# Power.net
KiCad netlist of a schematic drawn in Altium Designer
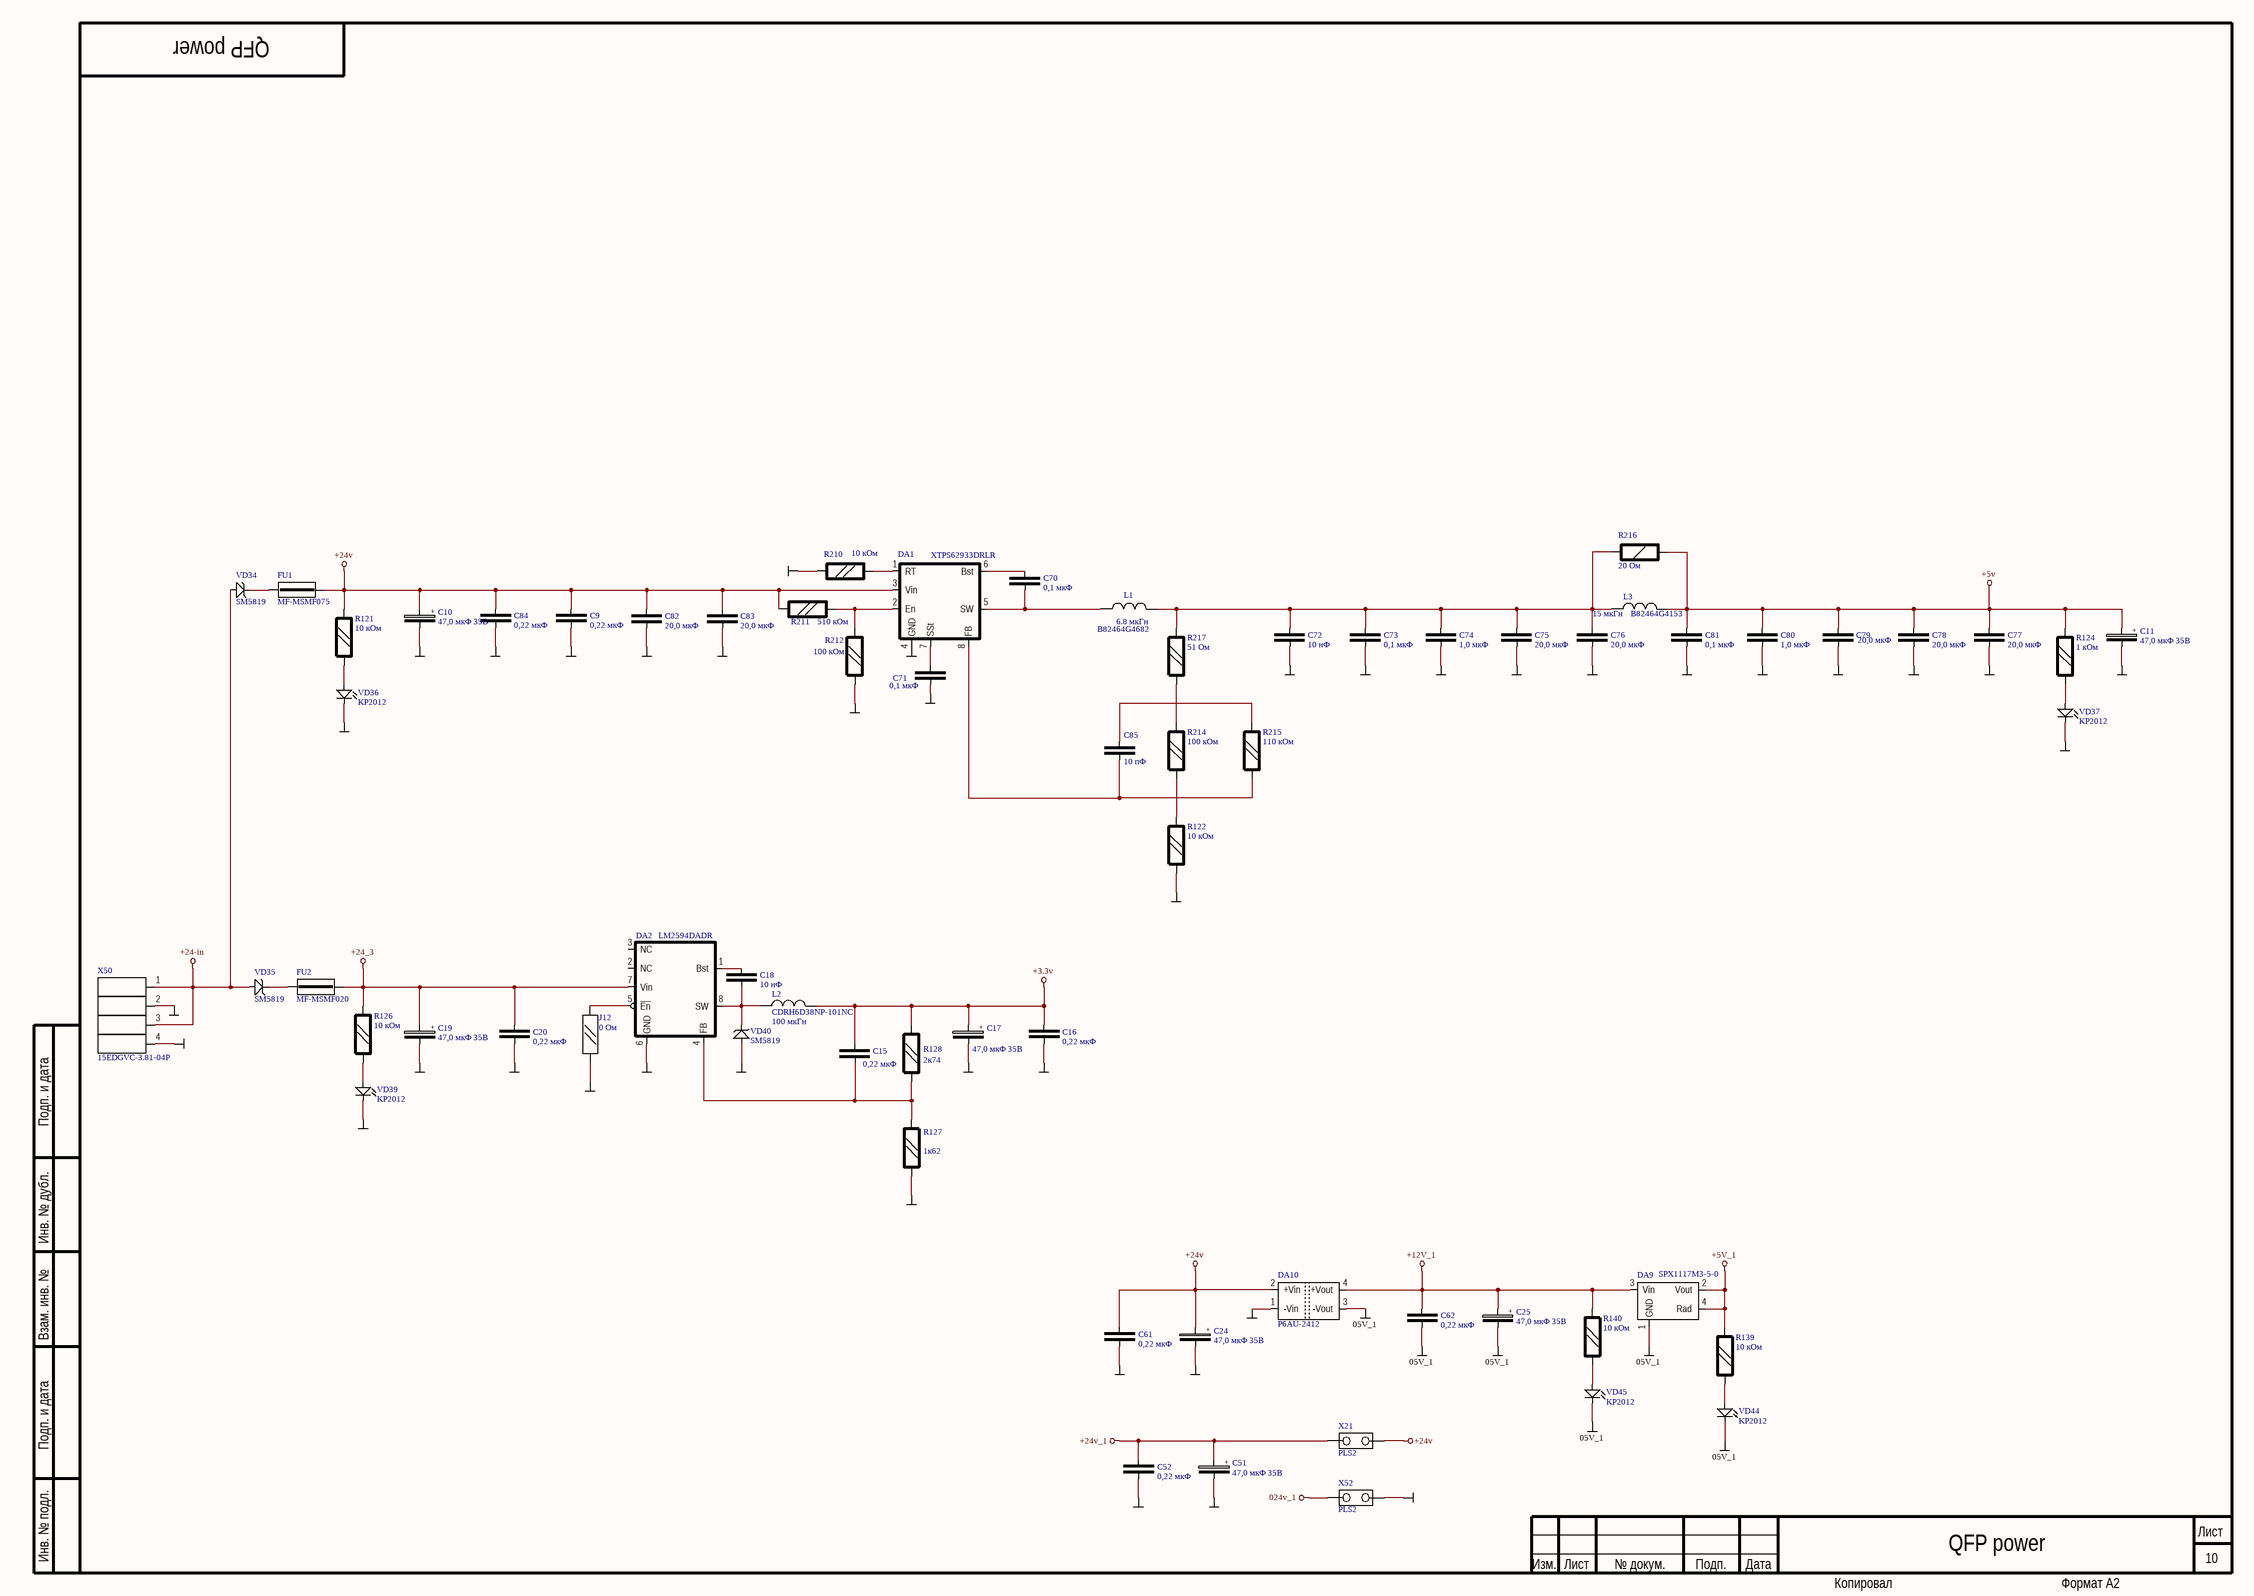
[diagram p0: Power.SchDoc]

(export (version "E")
  (design (tool "Eeschema 10.0.6"))
  (components
    (comp (ref "C9")
      (value "0,22 мкФ")
      (footprint "RC0805")
      (description "Чип конденсатор 0805")
      (fields (field (name "VOLTAGE") "50V"))
      (libsource (lib "L02_22F") (part "C0805Big"))
    )
    (comp (ref "C10")
      (value "47,0 мкФ 35В")
      (footprint "cap6")
      (description "5мм Электролитический конденсатор")
      (libsource (lib "SL02_22F") (part "C_e"))
    )
    (comp (ref "C11")
      (value "47,0 мкФ 35В")
      (footprint "cap6")
      (description "5мм Электролитический конденсатор")
      (libsource (lib "SL02_22F") (part "C_e"))
    )
    (comp (ref "C15")
      (value "0,22 мкФ")
      (footprint "SMD0805CAP")
      (description "Чип конденсатор 0805")
      (fields (field (name "VOLTAGE") "50V"))
      (libsource (lib "L02_22F") (part "C0805"))
    )
    (comp (ref "C16")
      (value "0,22 мкФ")
      (footprint "RC0805")
      (description "Чип конденсатор 0805")
      (fields (field (name "VOLTAGE") "50V"))
      (libsource (lib "L02_22F") (part "C0805Big"))
    )
    (comp (ref "C17")
      (value "47,0 мкФ 35В")
      (footprint "cap6")
      (description "5мм Электролитический конденсатор")
      (libsource (lib "SL02_22F") (part "C_e"))
    )
    (comp (ref "C18")
      (value "10 нФ")
      (footprint "RC0805")
      (description "Чип конденсатор 0805")
      (fields (field (name "VOLTAGE") "50V"))
      (libsource (lib "L02_22F") (part "C0805Big"))
    )
    (comp (ref "C19")
      (value "47,0 мкФ 35В")
      (footprint "cap6")
      (description "5мм Электролитический конденсатор")
      (libsource (lib "SL02_22F") (part "C_e"))
    )
    (comp (ref "C20")
      (value "0,22 мкФ")
      (footprint "RC0805")
      (description "Чип конденсатор 0805")
      (fields (field (name "VOLTAGE") "50V"))
      (libsource (lib "L02_22F") (part "C0805Big"))
    )
    (comp (ref "C24")
      (value "47,0 мкФ 35В")
      (footprint "cap6")
      (description "5мм Электролитический конденсатор")
      (libsource (lib "SL02_22F") (part "C_e"))
    )
    (comp (ref "C25")
      (value "47,0 мкФ 35В")
      (footprint "cap6")
      (description "5мм Электролитический конденсатор")
      (libsource (lib "SL02_22F") (part "C_e"))
    )
    (comp (ref "C51")
      (value "47,0 мкФ 35В")
      (footprint "cap6")
      (description "5мм Электролитический конденсатор")
      (libsource (lib "SL02_22F") (part "C_e"))
    )
    (comp (ref "C52")
      (value "0,22 мкФ")
      (footprint "SMD0805CAP")
      (description "Чип конденсатор 0805")
      (fields (field (name "VOLTAGE") "50V"))
      (libsource (lib "SL02_22F") (part "C0805"))
    )
    (comp (ref "C61")
      (value "0,22 мкФ")
      (footprint "SMD0805CAP")
      (description "Чип конденсатор 0805")
      (fields (field (name "VOLTAGE") "50V"))
      (libsource (lib "SL02_22F") (part "C0805"))
    )
    (comp (ref "C62")
      (value "0,22 мкФ")
      (footprint "SMD0805CAP")
      (description "Чип конденсатор 0805")
      (fields (field (name "VOLTAGE") "50V"))
      (libsource (lib "SL02_22F") (part "C0805"))
    )
    (comp (ref "C70")
      (value "0,1 мкФ")
      (footprint "SMD0805CAP")
      (description "Чип конденсатор 0805")
      (fields (field (name "VOLTAGE") "50V"))
      (libsource (lib "L02_22F") (part "C0805"))
    )
    (comp (ref "C71")
      (value "0,1 мкФ")
      (footprint "SMD0805CAP")
      (description "Чип конденсатор 0805")
      (fields (field (name "VOLTAGE") "50V"))
      (libsource (lib "L02_22F") (part "C0805"))
    )
    (comp (ref "C72")
      (value "10 нФ")
      (footprint "SMD0805CAP")
      (description "Чип конденсатор 0805")
      (fields (field (name "VOLTAGE") "50V"))
      (libsource (lib "L02_22F") (part "C0805"))
    )
    (comp (ref "C73")
      (value "0,1 мкФ")
      (footprint "SMD0805CAP")
      (description "Чип конденсатор 0805")
      (fields (field (name "VOLTAGE") "50V"))
      (libsource (lib "L02_22F") (part "C0805"))
    )
    (comp (ref "C74")
      (value "1,0 мкФ")
      (footprint "SMD0805CAP")
      (description "Чип конденсатор 0805")
      (fields (field (name "VOLTAGE") "50V"))
      (libsource (lib "L02_22F") (part "C0805"))
    )
    (comp (ref "C75")
      (value "20,0 мкФ")
      (footprint "CAPC1206")
      (description "Чип конденсатор 0805")
      (fields (field (name "VOLTAGE") "25V"))
      (libsource (lib "L02_22F") (part "C1206"))
    )
    (comp (ref "C76")
      (value "20,0 мкФ")
      (footprint "CAPC1206")
      (description "Чип конденсатор 0805")
      (fields (field (name "VOLTAGE") "25V"))
      (libsource (lib "L02_22F") (part "C1206"))
    )
    (comp (ref "C77")
      (value "20,0 мкФ")
      (footprint "CAPC1206")
      (description "Чип конденсатор 0805")
      (fields (field (name "VOLTAGE") "25V"))
      (libsource (lib "L02_22F") (part "C1206"))
    )
    (comp (ref "C78")
      (value "20,0 мкФ")
      (footprint "CAPC1206")
      (description "Чип конденсатор 0805")
      (fields (field (name "VOLTAGE") "25V"))
      (libsource (lib "L02_22F") (part "C1206"))
    )
    (comp (ref "C79")
      (value "20,0 мкФ")
      (footprint "CAPC1206")
      (description "Чип конденсатор 0805")
      (fields (field (name "VOLTAGE") "25V"))
      (libsource (lib "L02_22F") (part "C1206"))
    )
    (comp (ref "C80")
      (value "1,0 мкФ")
      (footprint "SMD0805CAP")
      (description "Чип конденсатор 0805")
      (fields (field (name "VOLTAGE") "50V"))
      (libsource (lib "L02_22F") (part "C0805"))
    )
    (comp (ref "C81")
      (value "0,1 мкФ")
      (footprint "SMD0805CAP")
      (description "Чип конденсатор 0805")
      (fields (field (name "VOLTAGE") "50V"))
      (libsource (lib "L02_22F") (part "C0805"))
    )
    (comp (ref "C82")
      (value "20,0 мкФ")
      (footprint "CAPC1206")
      (description "Чип конденсатор 0805")
      (fields (field (name "VOLTAGE") "25V"))
      (libsource (lib "L02_22F") (part "C1206"))
    )
    (comp (ref "C83")
      (value "20,0 мкФ")
      (footprint "CAPC1206")
      (description "Чип конденсатор 0805")
      (fields (field (name "VOLTAGE") "25V"))
      (libsource (lib "L02_22F") (part "C1206"))
    )
    (comp (ref "C84")
      (value "0,22 мкФ")
      (footprint "RC0805")
      (description "Чип конденсатор 0805")
      (fields (field (name "VOLTAGE") "50V"))
      (libsource (lib "L02_22F") (part "C0805Big"))
    )
    (comp (ref "C85")
      (value "10 пФ")
      (footprint "RC0805")
      (description "Чип конденсатор 0805")
      (fields (field (name "VOLTAGE") "50V"))
      (libsource (lib "L02_22F") (part "C0805Big"))
    )
    (comp (ref "DA1")
      (value "XTPS62933DRLR")
      (footprint "SOT583")
      (description "Понижающий DC/DC конвертор")
      (fields (field (name "VOLTAGE") "30V"))
      (libsource (lib "L02_22F") (part "XTPS62933DRLR"))
    )
    (comp (ref "DA2")
      (value "LM2594DADR")
      (footprint "SO8")
      (description "Понижающий DC/DC конвертор")
      (fields (field (name "VOLTAGE") "37V"))
      (libsource (lib "L02_22F") (part "LM2594DADR"))
    )
    (comp (ref "DA9")
      (value "SPX1117M3-5-0")
      (footprint "SOT223")
      (description "LDO стабилизатор")
      (fields (field (name "VOLTAGE") "20V"))
      (libsource (lib "SL02_22F") (part "SPX1117M3"))
    )
    (comp (ref "DA10")
      (value "P6AU-2412")
      (footprint "SiP4")
      (description "Изолированный DC-DC")
      (fields (field (name "VOLTAGE") "24V"))
      (libsource (lib "L02_22F") (part "P6AU"))
    )
    (comp (ref "FU1")
      (value "MF-MSMF075")
      (footprint "MSMF020")
      (description "Предохранитель самовосстанавливающийся")
      (libsource (lib "L02_22F") (part "MF-MSMF"))
    )
    (comp (ref "FU2")
      (value "MF-MSMF020")
      (footprint "MSMF020")
      (description "Предохранитель самовосстанавливающийся")
      (libsource (lib "L02_22F") (part "MF-MSMF"))
    )
    (comp (ref "J12")
      (value "0 Ом")
      (footprint "SMD0805RES")
      (description "SMD 0805 перемычка")
      (libsource (lib "L02_22F") (part "JR0805"))
    )
    (comp (ref "L1")
      (value "B82464G4682")
      (footprint "IND_COILCRAFT_MSS1038")
      (description "SMD Дроссель")
      (fields (field (name "INDUCTANCE") "6.8 мкГн"))
      (libsource (lib "L02_22F") (part "B82464G4"))
    )
    (comp (ref "L2")
      (value "CDRH6D38NP-101NC")
      (footprint "cdrh6d38np")
      (description "SMD Дроссель")
      (fields (field (name "INDUCTANCE") "100 мкГн"))
      (libsource (lib "L02_22F") (part "CDRH6D38NP"))
    )
    (comp (ref "L3")
      (value "B82464G4153")
      (footprint "IND_COILCRAFT_MSS1038")
      (description "SMD Дроссель")
      (fields (field (name "INDUCTANCE") "15 мкГн"))
      (libsource (lib "L02_22F") (part "B82464G4"))
    )
    (comp (ref "R121")
      (value "10 кОм")
      (footprint "SMD0805RES")
      (description "Чип резистор 0805")
      (fields (field (name "TOLERANCE") "5%"))
      (libsource (lib "L02_22F") (part "R0805"))
    )
    (comp (ref "R122")
      (value "10 кОм")
      (footprint "SMD0805RES")
      (description "Чип резистор 0805")
      (fields (field (name "TOLERANCE") "1%"))
      (libsource (lib "L02_22F") (part "R0805"))
    )
    (comp (ref "R124")
      (value "1 кОм")
      (footprint "SMD0805RES")
      (description "Чип резистор 0805")
      (fields (field (name "TOLERANCE") "5%"))
      (libsource (lib "SL02_22F") (part "R0805"))
    )
    (comp (ref "R126")
      (value "10 кОм")
      (footprint "SMD0805RES")
      (description "Чип резистор 0805")
      (fields (field (name "TOLERANCE") "5%"))
      (libsource (lib "L02_22F") (part "R0805"))
    )
    (comp (ref "R127")
      (value "1к62")
      (footprint "SMD0805RES")
      (description "Чип резистор 0805")
      (fields (field (name "TOLERANCE") "1%"))
      (libsource (lib "L02_22F") (part "R0805"))
    )
    (comp (ref "R128")
      (value "2к74")
      (footprint "SMD0805RES")
      (description "Чип резистор 0805")
      (fields (field (name "TOLERANCE") "1%"))
      (libsource (lib "L02_22F") (part "R0805"))
    )
    (comp (ref "R139")
      (value "10 кОм")
      (footprint "SMD0805RES")
      (description "Чип резистор 0805")
      (fields (field (name "TOLERANCE") "5%"))
      (libsource (lib "SL02_22F") (part "R0805"))
    )
    (comp (ref "R140")
      (value "10 кОм")
      (footprint "SMD0805RES")
      (description "Чип резистор 0805")
      (fields (field (name "TOLERANCE") "5%"))
      (libsource (lib "SL02_22F") (part "R0805"))
    )
    (comp (ref "R210")
      (value "10 кОм")
      (footprint "SMD0805RES")
      (description "Чип резистор 0805")
      (fields (field (name "TOLERANCE") "1%"))
      (libsource (lib "L02_22F") (part "R0805"))
    )
    (comp (ref "R211")
      (value "510 кОм")
      (footprint "SMD0805RES")
      (description "Чип резистор 0805")
      (fields (field (name "TOLERANCE") "5%"))
      (libsource (lib "L02_22F") (part "R0805"))
    )
    (comp (ref "R212")
      (value "100 кОм")
      (footprint "SMD0805RES")
      (description "Чип резистор 0805")
      (fields (field (name "TOLERANCE") "5%"))
      (libsource (lib "L02_22F") (part "R0805"))
    )
    (comp (ref "R214")
      (value "100 кОм")
      (footprint "SMD0805RES")
      (description "Чип резистор 0805")
      (fields (field (name "TOLERANCE") "1%"))
      (libsource (lib "L02_22F") (part "R0805"))
    )
    (comp (ref "R215")
      (value "110 кОм")
      (footprint "SMD0805RES")
      (description "Чип резистор 0805")
      (fields (field (name "TOLERANCE") "1%"))
      (libsource (lib "L02_22F") (part "R0805"))
    )
    (comp (ref "R216")
      (value "20 Ом")
      (footprint "RES1206")
      (description "Чип резистор 1206")
      (fields (field (name "TOLERANCE") "5%"))
      (libsource (lib "L02_22F") (part "R1206"))
    )
    (comp (ref "R217")
      (value "51 Ом")
      (footprint "SMD0805RES")
      (description "Чип резистор 0805")
      (fields (field (name "TOLERANCE") "5%"))
      (libsource (lib "L02_22F") (part "R0805"))
    )
    (comp (ref "VD34")
      (value "SM5819")
      (footprint "MELF")
      (description "Чип шоттки диод MELF")
      (fields (field (name "VOLTAGE") "40V"))
      (libsource (lib "L02_22F") (part "SM5819"))
    )
    (comp (ref "VD35")
      (value "SM5819")
      (footprint "MELF")
      (description "Чип шоттки диод MELF")
      (fields (field (name "VOLTAGE") "40V"))
      (libsource (lib "L02_22F") (part "SM5819"))
    )
    (comp (ref "VD36")
      (value "KP2012")
      (footprint "SMD0805DIO_C")
      (description "Чип светодиод 0805")
      (libsource (lib "L02_22F") (part "KP2012_C"))
    )
    (comp (ref "VD37")
      (value "KP2012")
      (footprint "SMD0805DIO_C")
      (description "Чип светодиод 0805")
      (libsource (lib "L02_22F") (part "KP2012_C"))
    )
    (comp (ref "VD39")
      (value "KP2012")
      (footprint "SMD0805DIO_C")
      (description "Чип светодиод 0805")
      (libsource (lib "L02_22F") (part "KP2012_C"))
    )
    (comp (ref "VD40")
      (value "SM5819")
      (footprint "MELF")
      (description "Чип шоттки диод MELF")
      (fields (field (name "VOLTAGE") "40V"))
      (libsource (lib "L02_22F") (part "SM5819"))
    )
    (comp (ref "VD44")
      (value "KP2012")
      (footprint "SMD0805DIO_C")
      (description "Чип светодиод 0805")
      (libsource (lib "L02_22F") (part "KP2012_C"))
    )
    (comp (ref "VD45")
      (value "KP2012")
      (footprint "SMD0805DIO_C")
      (description "Чип светодиод 0805")
      (libsource (lib "L02_22F") (part "KP2012_C"))
    )
    (comp (ref "X21")
      (value "PLS2")
      (footprint "PLS2")
      (description "Джампер PLS2 2.54мм")
      (libsource (lib "L02_22F") (part "PLS2"))
    )
    (comp (ref "X50")
      (value "15EDGVC-3.81-04P")
      (footprint "15EDGVC_081_4")
      (description "Вилка  4/3.81")
      (fields (field (name "VOLTAGE") "2кВ"))
      (libsource (lib "L02_22F") (part "15EDGVC-3.81-04P"))
    )
    (comp (ref "X52")
      (value "PLS2")
      (footprint "PLS2")
      (description "Джампер PLS2 2.54мм")
      (libsource (lib "L02_22F") (part "PLS2"))
    )
  )
  (nets
    (net (code "1") (name "+3.3v") (class "Default")
      (node (ref "C15") (pin "2") (pinfunction "2_2") (pintype "passive"))
      (node (ref "C16") (pin "1") (pinfunction "1_1") (pintype "passive"))
      (node (ref "C17") (pin "1") (pinfunction "+_1") (pintype "passive"))
      (node (ref "L2") (pin "1") (pinfunction "1_1") (pintype "passive"))
      (node (ref "R128") (pin "2") (pinfunction "2_2") (pintype "passive"))
    )
    (net (code "2") (name "+5V_1") (class "Default")
      (node (ref "DA9") (pin "2") (pinfunction "Vout_2") (pintype "power_in"))
      (node (ref "DA9") (pin "4") (pinfunction "Rad_4") (pintype "power_in"))
      (node (ref "R139") (pin "1") (pinfunction "1_1") (pintype "passive"))
    )
    (net (code "3") (name "+5v") (class "Default")
      (node (ref "C11") (pin "1") (pinfunction "+_1") (pintype "passive"))
      (node (ref "C77") (pin "2") (pinfunction "2_2") (pintype "passive"))
      (node (ref "C78") (pin "2") (pinfunction "2_2") (pintype "passive"))
      (node (ref "C79") (pin "2") (pinfunction "2_2") (pintype "passive"))
      (node (ref "C80") (pin "2") (pinfunction "2_2") (pintype "passive"))
      (node (ref "C81") (pin "2") (pinfunction "2_2") (pintype "passive"))
      (node (ref "L3") (pin "2") (pinfunction "2_2") (pintype "passive"))
      (node (ref "R124") (pin "2") (pinfunction "2_2") (pintype "passive"))
      (node (ref "R216") (pin "2") (pinfunction "2_2") (pintype "passive"))
    )
    (net (code "4") (name "+12V_1") (class "Default")
      (node (ref "C25") (pin "1") (pinfunction "+_1") (pintype "passive"))
      (node (ref "C62") (pin "1") (pinfunction "1_1") (pintype "passive"))
      (node (ref "DA10") (pin "4") (pinfunction "+Vout_4") (pintype "power_in"))
      (node (ref "DA9") (pin "3") (pinfunction "Vin_3") (pintype "power_in"))
      (node (ref "R140") (pin "1") (pinfunction "1_1") (pintype "passive"))
    )
    (net (code "5") (name "+24-in") (class "Default")
      (node (ref "VD34") (pin "2") (pinfunction "Anode_2") (pintype "passive"))
      (node (ref "VD35") (pin "2") (pinfunction "Anode_2") (pintype "passive"))
      (node (ref "X50") (pin "1") (pinfunction "1_1") (pintype "passive"))
      (node (ref "X50") (pin "3") (pinfunction "3_3") (pintype "passive"))
    )
    (net (code "6") (name "+24_3") (class "Default")
      (node (ref "C19") (pin "1") (pinfunction "+_1") (pintype "passive"))
      (node (ref "C20") (pin "1") (pinfunction "1_1") (pintype "passive"))
      (node (ref "DA2") (pin "7") (pinfunction "Vin_7") (pintype "power_in"))
      (node (ref "FU2") (pin "1") (pinfunction "1_1") (pintype "passive"))
      (node (ref "R126") (pin "2") (pinfunction "2_2") (pintype "passive"))
    )
    (net (code "7") (name "+24v") (class "Default")
      (node (ref "C10") (pin "1") (pinfunction "+_1") (pintype "passive"))
      (node (ref "C24") (pin "1") (pinfunction "+_1") (pintype "passive"))
      (node (ref "C61") (pin "1") (pinfunction "1_1") (pintype "passive"))
      (node (ref "C82") (pin "2") (pinfunction "2_2") (pintype "passive"))
      (node (ref "C83") (pin "2") (pinfunction "2_2") (pintype "passive"))
      (node (ref "C84") (pin "1") (pinfunction "1_1") (pintype "passive"))
      (node (ref "C9") (pin "1") (pinfunction "1_1") (pintype "passive"))
      (node (ref "DA1") (pin "3") (pinfunction "Vin_3") (pintype "power_in"))
      (node (ref "DA10") (pin "2") (pinfunction "+Vin_2") (pintype "power_in"))
      (node (ref "FU1") (pin "1") (pinfunction "1_1") (pintype "passive"))
      (node (ref "R121") (pin "2") (pinfunction "2_2") (pintype "passive"))
      (node (ref "R211") (pin "1") (pinfunction "1_1") (pintype "passive"))
      (node (ref "X21") (pin "2") (pinfunction "2_2") (pintype "passive"))
    )
    (net (code "8") (name "+24v_1") (class "Default")
      (node (ref "C51") (pin "1") (pinfunction "+_1") (pintype "passive"))
      (node (ref "C52") (pin "1") (pinfunction "1_1") (pintype "passive"))
      (node (ref "X21") (pin "1") (pinfunction "1_1") (pintype "passive"))
    )
    (net (code "9") (name "05V_1") (class "Default")
      (node (ref "C25") (pin "2") (pinfunction "-_2") (pintype "passive"))
      (node (ref "C62") (pin "2") (pinfunction "2_2") (pintype "passive"))
      (node (ref "DA10") (pin "3") (pinfunction "-Vout_3") (pintype "power_in"))
      (node (ref "DA9") (pin "1") (pinfunction "GND_1") (pintype "power_in"))
      (node (ref "VD44") (pin "1") (pinfunction "Cathode_1") (pintype "passive"))
      (node (ref "VD45") (pin "1") (pinfunction "Cathode_1") (pintype "passive"))
    )
    (net (code "10") (name "024v_1") (class "Default")
      (node (ref "X52") (pin "1") (pinfunction "1_1") (pintype "passive"))
    )
    (net (code "11") (name "GND") (class "Default")
      (node (ref "C10") (pin "2") (pinfunction "-_2") (pintype "passive"))
      (node (ref "C11") (pin "2") (pinfunction "-_2") (pintype "passive"))
      (node (ref "C16") (pin "2") (pinfunction "2_2") (pintype "passive"))
      (node (ref "C17") (pin "2") (pinfunction "-_2") (pintype "passive"))
      (node (ref "C19") (pin "2") (pinfunction "-_2") (pintype "passive"))
      (node (ref "C20") (pin "2") (pinfunction "2_2") (pintype "passive"))
      (node (ref "C24") (pin "2") (pinfunction "-_2") (pintype "passive"))
      (node (ref "C51") (pin "2") (pinfunction "-_2") (pintype "passive"))
      (node (ref "C52") (pin "2") (pinfunction "2_2") (pintype "passive"))
      (node (ref "C61") (pin "2") (pinfunction "2_2") (pintype "passive"))
      (node (ref "C71") (pin "1") (pinfunction "1_1") (pintype "passive"))
      (node (ref "C72") (pin "1") (pinfunction "1_1") (pintype "passive"))
      (node (ref "C73") (pin "1") (pinfunction "1_1") (pintype "passive"))
      (node (ref "C74") (pin "1") (pinfunction "1_1") (pintype "passive"))
      (node (ref "C75") (pin "1") (pinfunction "1_1") (pintype "passive"))
      (node (ref "C76") (pin "1") (pinfunction "1_1") (pintype "passive"))
      (node (ref "C77") (pin "1") (pinfunction "1_1") (pintype "passive"))
      (node (ref "C78") (pin "1") (pinfunction "1_1") (pintype "passive"))
      (node (ref "C79") (pin "1") (pinfunction "1_1") (pintype "passive"))
      (node (ref "C80") (pin "1") (pinfunction "1_1") (pintype "passive"))
      (node (ref "C81") (pin "1") (pinfunction "1_1") (pintype "passive"))
      (node (ref "C82") (pin "1") (pinfunction "1_1") (pintype "passive"))
      (node (ref "C83") (pin "1") (pinfunction "1_1") (pintype "passive"))
      (node (ref "C84") (pin "2") (pinfunction "2_2") (pintype "passive"))
      (node (ref "C9") (pin "2") (pinfunction "2_2") (pintype "passive"))
      (node (ref "DA1") (pin "4") (pinfunction "GND_4") (pintype "power_in"))
      (node (ref "DA10") (pin "1") (pinfunction "-Vin_1") (pintype "power_in"))
      (node (ref "DA2") (pin "6") (pinfunction "GND_6") (pintype "power_in"))
      (node (ref "J12") (pin "2") (pinfunction "2_2") (pintype "passive"))
      (node (ref "R122") (pin "1") (pinfunction "1_1") (pintype "passive"))
      (node (ref "R127") (pin "2") (pinfunction "2_2") (pintype "passive"))
      (node (ref "R210") (pin "1") (pinfunction "1_1") (pintype "passive"))
      (node (ref "R212") (pin "1") (pinfunction "1_1") (pintype "passive"))
      (node (ref "VD36") (pin "1") (pinfunction "Cathode_1") (pintype "passive"))
      (node (ref "VD37") (pin "1") (pinfunction "Cathode_1") (pintype "passive"))
      (node (ref "VD39") (pin "1") (pinfunction "Cathode_1") (pintype "passive"))
      (node (ref "VD40") (pin "2") (pinfunction "Anode_2") (pintype "passive"))
      (node (ref "X50") (pin "2") (pinfunction "2_2") (pintype "passive"))
      (node (ref "X50") (pin "4") (pinfunction "4_4") (pintype "passive"))
      (node (ref "X52") (pin "2") (pinfunction "2_2") (pintype "passive"))
    )
    (net (code "12") (name "Net-(C72-Pad2)") (class "Default")
      (node (ref "C72") (pin "2") (pinfunction "2_2") (pintype "passive"))
      (node (ref "C73") (pin "2") (pinfunction "2_2") (pintype "passive"))
      (node (ref "C74") (pin "2") (pinfunction "2_2") (pintype "passive"))
      (node (ref "C75") (pin "2") (pinfunction "2_2") (pintype "passive"))
      (node (ref "C76") (pin "2") (pinfunction "2_2") (pintype "passive"))
      (node (ref "L1") (pin "2") (pinfunction "2_2") (pintype "passive"))
      (node (ref "L3") (pin "1") (pinfunction "1_1") (pintype "passive"))
      (node (ref "R216") (pin "1") (pinfunction "1_1") (pintype "passive"))
      (node (ref "R217") (pin "2") (pinfunction "2_2") (pintype "passive"))
    )
    (net (code "13") (name "Net-(C85-Pad1)") (class "Default")
      (node (ref "C85") (pin "1") (pinfunction "1_1") (pintype "passive"))
      (node (ref "R215") (pin "2") (pinfunction "2_2") (pintype "passive"))
    )
    (net (code "14") (name "Net-(DA1-Bst)") (class "Default")
      (node (ref "C70") (pin "2") (pinfunction "2_2") (pintype "passive"))
      (node (ref "DA1") (pin "6") (pinfunction "Bst_6") (pintype "passive"))
    )
    (net (code "15") (name "Net-(DA1-En)") (class "Default")
      (node (ref "DA1") (pin "2") (pinfunction "En_2") (pintype "input"))
      (node (ref "R211") (pin "2") (pinfunction "2_2") (pintype "passive"))
      (node (ref "R212") (pin "2") (pinfunction "2_2") (pintype "passive"))
    )
    (net (code "16") (name "Net-(DA1-FB)") (class "Default")
      (node (ref "C85") (pin "2") (pinfunction "2_2") (pintype "passive"))
      (node (ref "DA1") (pin "8") (pinfunction "FB_8") (pintype "passive"))
      (node (ref "R215") (pin "1") (pinfunction "1_1") (pintype "passive"))
    )
    (net (code "17") (name "Net-(DA1-RT)") (class "Default")
      (node (ref "DA1") (pin "1") (pinfunction "RT_1") (pintype "passive"))
      (node (ref "R210") (pin "2") (pinfunction "2_2") (pintype "passive"))
    )
    (net (code "18") (name "Net-(DA1-SSt)") (class "Default")
      (node (ref "C71") (pin "2") (pinfunction "2_2") (pintype "passive"))
      (node (ref "DA1") (pin "7") (pinfunction "SSt_7") (pintype "passive"))
    )
    (net (code "19") (name "Net-(DA1-SW)") (class "Default")
      (node (ref "C70") (pin "1") (pinfunction "1_1") (pintype "passive"))
      (node (ref "DA1") (pin "5") (pinfunction "SW_5") (pintype "output"))
      (node (ref "L1") (pin "1") (pinfunction "1_1") (pintype "passive"))
    )
    (net (code "20") (name "Net-(DA2-Bst)") (class "Default")
      (node (ref "C18") (pin "1") (pinfunction "1_1") (pintype "passive"))
      (node (ref "DA2") (pin "1") (pinfunction "Bst_1") (pintype "passive"))
    )
    (net (code "21") (name "Net-(DA2-En)") (class "Default")
      (node (ref "DA2") (pin "5") (pinfunction "En_5") (pintype "input"))
      (node (ref "J12") (pin "1") (pinfunction "1_1") (pintype "passive"))
    )
    (net (code "22") (name "Net-(DA2-FB)") (class "Default")
      (node (ref "C15") (pin "1") (pinfunction "1_1") (pintype "passive"))
      (node (ref "DA2") (pin "4") (pinfunction "FB_4") (pintype "passive"))
      (node (ref "R127") (pin "1") (pinfunction "1_1") (pintype "passive"))
      (node (ref "R128") (pin "1") (pinfunction "1_1") (pintype "passive"))
    )
    (net (code "23") (name "Net-(DA2-SW)") (class "Default")
      (node (ref "C18") (pin "2") (pinfunction "2_2") (pintype "passive"))
      (node (ref "DA2") (pin "8") (pinfunction "SW_8") (pintype "output"))
      (node (ref "L2") (pin "2") (pinfunction "2_2") (pintype "passive"))
      (node (ref "VD40") (pin "1") (pinfunction "Cathode_1") (pintype "passive"))
    )
    (net (code "24") (name "Net-(R122-Pad2)") (class "Default")
      (node (ref "R122") (pin "2") (pinfunction "2_2") (pintype "passive"))
      (node (ref "R214") (pin "1") (pinfunction "1_1") (pintype "passive"))
    )
    (net (code "25") (name "Net-(R214-Pad2)") (class "Default")
      (node (ref "R214") (pin "2") (pinfunction "2_2") (pintype "passive"))
      (node (ref "R217") (pin "1") (pinfunction "1_1") (pintype "passive"))
    )
    (net (code "26") (name "Net-(VD34-Cathode)") (class "Default")
      (node (ref "FU1") (pin "2") (pinfunction "2_2") (pintype "passive"))
      (node (ref "VD34") (pin "1") (pinfunction "Cathode_1") (pintype "passive"))
    )
    (net (code "27") (name "Net-(VD35-Cathode)") (class "Default")
      (node (ref "FU2") (pin "2") (pinfunction "2_2") (pintype "passive"))
      (node (ref "VD35") (pin "1") (pinfunction "Cathode_1") (pintype "passive"))
    )
    (net (code "28") (name "Net-(VD36-Anode)") (class "Default")
      (node (ref "R121") (pin "1") (pinfunction "1_1") (pintype "passive"))
      (node (ref "VD36") (pin "2") (pinfunction "Anode_2") (pintype "passive"))
    )
    (net (code "29") (name "Net-(VD37-Anode)") (class "Default")
      (node (ref "R124") (pin "1") (pinfunction "1_1") (pintype "passive"))
      (node (ref "VD37") (pin "2") (pinfunction "Anode_2") (pintype "passive"))
    )
    (net (code "30") (name "Net-(VD39-Anode)") (class "Default")
      (node (ref "R126") (pin "1") (pinfunction "1_1") (pintype "passive"))
      (node (ref "VD39") (pin "2") (pinfunction "Anode_2") (pintype "passive"))
    )
    (net (code "31") (name "Net-(VD44-Anode)") (class "Default")
      (node (ref "R139") (pin "2") (pinfunction "2_2") (pintype "passive"))
      (node (ref "VD44") (pin "2") (pinfunction "Anode_2") (pintype "passive"))
    )
    (net (code "32") (name "Net-(VD45-Anode)") (class "Default")
      (node (ref "R140") (pin "2") (pinfunction "2_2") (pintype "passive"))
      (node (ref "VD45") (pin "2") (pinfunction "Anode_2") (pintype "passive"))
    )
    (net (code "33") (name "unconnected-(DA2-NC-Pad2)") (class "Default")
      (node (ref "DA2") (pin "2") (pinfunction "NC_2") (pintype "passive"))
    )
    (net (code "34") (name "unconnected-(DA2-NC-Pad3)") (class "Default")
      (node (ref "DA2") (pin "3") (pinfunction "NC_3") (pintype "passive"))
    )
  )
)
